# design.net
KiCad netlist of a schematic drawn in Altium Designer
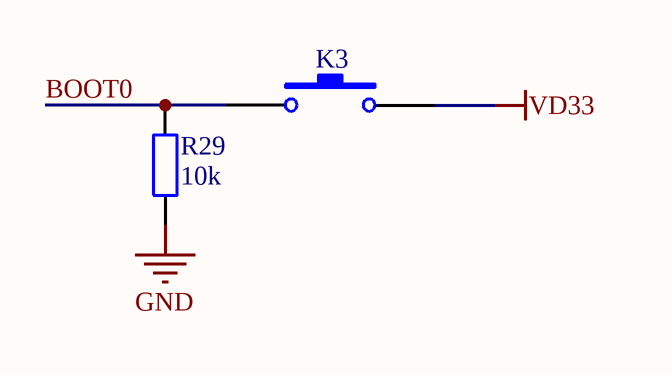
[diagram p0: 启动模式.SchDoc]

(export (version "E")
  (design (tool "Eeschema 10.0.6"))
  (components
    (comp (ref "K3")
      (value "�ᴥ����")
      (footprint "SW6X6")
      (description "�ᴥ����6��6mm,�Ľǲ��")
      (fields (field (name "PUBLISHER") "Altium Limited"))
      (libsource (lib "ECG") (part "SW-PB"))
    )
    (comp (ref "R29")
      (value "10k")
      (footprint "LC-0805_R")
      (description "10k��,0805,��5%")
      (libsource (lib "ECG") (part "R"))
    )
  )
  (nets
    (net (code "1") (name "/BOOT0") (class "Default")
      (node (ref "K3") (pin "1") (pinfunction "1_1") (pintype "passive"))
      (node (ref "R29") (pin "2") (pintype "passive"))
    )
    (net (code "2") (name "GND") (class "Default") (node (ref "R29") (pin "1") (pintype "passive")))
    (net (code "3") (name "VD33") (class "Default")
      (node (ref "K3") (pin "2") (pinfunction "2_2") (pintype "passive"))
    )
  )
)
